# Sheet1.net
KiCad netlist of a schematic drawn in Altium Designer
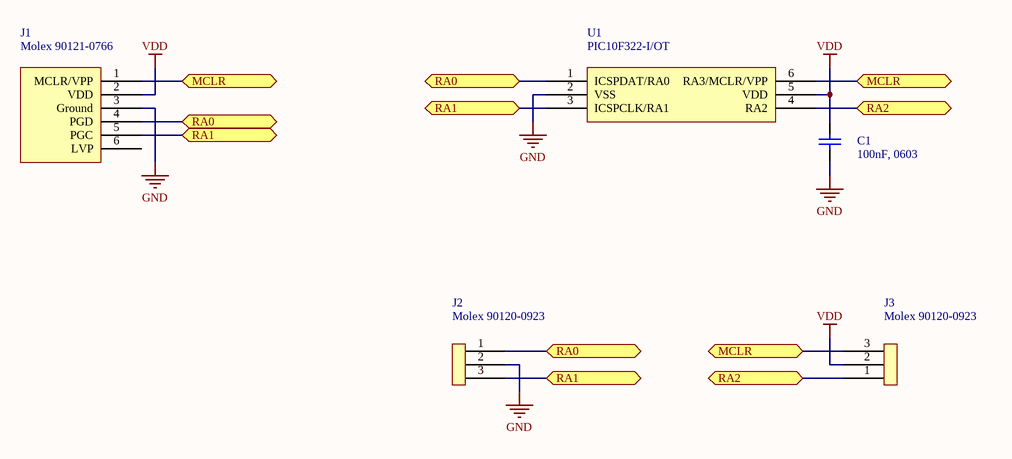
[diagram p0: Sheet1.SchDoc]

(export (version "E")
  (design (tool "Eeschema 10.0.6"))
  (components
    (comp (ref "C1")
      (value "100nF, 0603")
      (footprint "Capacitor 0603")
      (libsource (lib "x-io") (part "Capacitor"))
    )
    (comp (ref "J1")
      (value "Molex 90121-0766")
      (footprint "Molex 90121-0766")
      (libsource (lib "x-io") (part "MPLAB ICSP"))
    )
    (comp (ref "J2")
      (value "Molex 90120-0923")
      (footprint "Molex 90120-0923")
      (libsource (lib "") (part "Molex 90120-0923_1"))
    )
    (comp (ref "J3")
      (value "Molex 90120-0923")
      (footprint "Molex 90120-0923")
      (libsource (lib "x-io") (part "Molex 90120-0923"))
    )
    (comp (ref "U1")
      (value "PIC10F322-I/OT")
      (footprint "SOT-23-6")
      (libsource (lib "x-io") (part "PIC10F322-I/OT"))
    )
  )
  (nets
    (net (code "1") (name "/MCLR") (class "Default")
      (node (ref "J1") (pin "1") (pinfunction "MCLR/VPP_1") (pintype "passive"))
      (node (ref "J3") (pin "3") (pinfunction "3_3") (pintype "passive"))
      (node (ref "U1") (pin "6") (pinfunction "RA3/MCLR/VPP_6") (pintype "passive"))
    )
    (net (code "2") (name "/RA0") (class "Default")
      (node (ref "J1") (pin "4") (pinfunction "PGD_4") (pintype "passive"))
      (node (ref "J2") (pin "1") (pinfunction "1_1") (pintype "passive"))
      (node (ref "U1") (pin "1") (pinfunction "ICSPDAT/RA0_1") (pintype "passive"))
    )
    (net (code "3") (name "/RA1") (class "Default")
      (node (ref "J1") (pin "5") (pinfunction "PGC_5") (pintype "passive"))
      (node (ref "J2") (pin "3") (pinfunction "3_3") (pintype "passive"))
      (node (ref "U1") (pin "3") (pinfunction "ICSPCLK/RA1_3") (pintype "passive"))
    )
    (net (code "4") (name "/RA2") (class "Default")
      (node (ref "J3") (pin "1") (pinfunction "1_1") (pintype "passive"))
      (node (ref "U1") (pin "4") (pinfunction "RA2_4") (pintype "passive"))
    )
    (net (code "5") (name "GND") (class "Default")
      (node (ref "C1") (pin "1") (pinfunction "1_1") (pintype "passive"))
      (node (ref "J1") (pin "3") (pinfunction "Ground_3") (pintype "passive"))
      (node (ref "J2") (pin "2") (pinfunction "2_2") (pintype "passive"))
      (node (ref "U1") (pin "2") (pinfunction "VSS_2") (pintype "passive"))
    )
    (net (code "6") (name "VDD") (class "Default")
      (node (ref "C1") (pin "2") (pinfunction "2_2") (pintype "passive"))
      (node (ref "J1") (pin "2") (pinfunction "VDD_2") (pintype "passive"))
      (node (ref "J3") (pin "2") (pinfunction "2_2") (pintype "passive"))
      (node (ref "U1") (pin "5") (pinfunction "VDD_5") (pintype "passive"))
    )
    (net (code "7") (name "unconnected-(J1-LVP-Pad6)") (class "Default")
      (node (ref "J1") (pin "6") (pinfunction "LVP_6") (pintype "passive"))
    )
  )
)
